# 7-Latching_IMD.net
KiCad netlist of a schematic drawn in Altium Designer
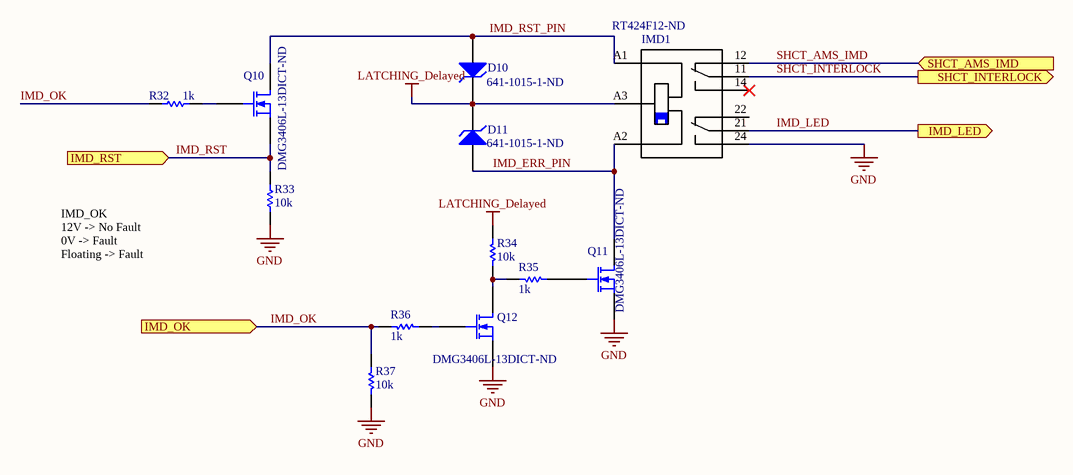
[diagram p0: 7-Latching IMD.SchDoc]

(export (version "E")
  (design (tool "Eeschema 10.0.6"))
  (components
    (comp (ref "D10")
      (value "D Zener")
      (footprint "DO214AC")
      (description "Zener Diode")
      (fields
        (field (name "SUPPLIER PART NUMBER 1") "641-1015-1-ND")
        (field (name "PUBLISHER") "Altium Limited")
      )
      (libsource (lib "Miscellaneous Devices") (part "D Zener"))
    )
    (comp (ref "D11")
      (value "D Zener")
      (footprint "DO214AC")
      (description "Zener Diode")
      (fields
        (field (name "SUPPLIER PART NUMBER 1") "641-1015-1-ND")
        (field (name "PUBLISHER") "Altium Limited")
      )
      (libsource (lib "Miscellaneous Devices") (part "D Zener"))
    )
    (comp (ref "IMD1")
      (value "5-1393243-4")
      (footprint "TE_5-1393243-4")
      (description "Electromechanical Relay 12VDC 240Ohm 15A DPDT __ 29mm 12.7mm 15.7mm__ THT Power Relay")
      (fields (field (name "MF") "TE Connectivity") (field (name "SUPPLIER PART NUMBER 1") "RT424F12-ND"))
      (libsource (lib "5-1393243-4") (part "5-1393243-4"))
    )
    (comp (ref "Q10")
      (value "~")
      (footprint "SOT-23_N")
      (description "N-Channel MOSFET")
      (fields
        (field (name "MANUFACTURER") "Infineon Technologies")
        (field (name "SUPPLIER PART NUMBER 1") "DMG3406L-13DICT-ND")
        (field (name "PUBLISHER") "Altium Limited")
      )
      (libsource (lib "Miscellaneous Devices") (part "MOSFET-N"))
    )
    (comp (ref "Q11")
      (value "~")
      (footprint "SOT-23_N")
      (description "N-Channel MOSFET")
      (fields
        (field (name "MANUFACTURER") "Infineon Technologies")
        (field (name "SUPPLIER PART NUMBER 1") "DMG3406L-13DICT-ND")
        (field (name "PUBLISHER") "Altium Limited")
      )
      (libsource (lib "Miscellaneous Devices") (part "MOSFET-N"))
    )
    (comp (ref "Q12")
      (value "~")
      (footprint "SOT-23_N")
      (description "N-Channel MOSFET")
      (fields
        (field (name "MANUFACTURER") "Infineon Technologies")
        (field (name "SUPPLIER PART NUMBER 1") "DMG3406L-13DICT-ND")
        (field (name "PUBLISHER") "Altium Limited")
      )
      (libsource (lib "Miscellaneous Devices") (part "MOSFET-N"))
    )
    (comp (ref "R32")
      (value "1k")
      (footprint "1608[0603]")
      (description "RES SMD 100 OHM 5% 1/4W 0603")
      (fields
        (field (name "MANUFACTURER") "Rohm Semiconductor")
        (field (name "MANUFACTURER PART NUMBER") "ESR03EZPJ101")
        (field (name "PUBLISHER") "Altium Limited")
      )
      (libsource (lib "Miscellaneous Devices") (part "Res1"))
    )
    (comp (ref "R33")
      (value "10k")
      (footprint "1608[0603]")
      (description "RES SMD 10K OHM 5% 1/4W 0603")
      (fields
        (field (name "MANUFACTURER") "Rohm Semiconductor")
        (field (name "MANUFACTURER PART NUMBER") "ESR03EZPJ103")
        (field (name "PUBLISHER") "Altium Limited")
      )
      (libsource (lib "Miscellaneous Devices") (part "Res1"))
    )
    (comp (ref "R34")
      (value "RHM1.0KDCT-ND")
      (footprint "1608[0603]")
      (description "RES SMD 1.0K OHM 5% 1/4W 0603")
      (fields
        (field (name "MANUFACTURER") "Rohm Semiconductor")
        (field (name "MANUFACTURER PART NUMBER") "ESR03EZPJ102")
        (field (name "RESISTANCE (OHMS)") "10k")
      )
      (libsource (lib "Miscellaneous Devices") (part "Res1"))
    )
    (comp (ref "R35")
      (value "1k")
      (footprint "1608[0603]")
      (description "RES SMD 100 OHM 5% 1/4W 0603")
      (fields
        (field (name "MANUFACTURER") "Rohm Semiconductor")
        (field (name "MANUFACTURER PART NUMBER") "ESR03EZPJ101")
        (field (name "PUBLISHER") "Altium Limited")
      )
      (libsource (lib "Miscellaneous Devices") (part "Res1"))
    )
    (comp (ref "R36")
      (value "1k")
      (footprint "1608[0603]")
      (description "RES SMD 100 OHM 5% 1/4W 0603")
      (fields
        (field (name "MANUFACTURER") "Rohm Semiconductor")
        (field (name "MANUFACTURER PART NUMBER") "ESR03EZPJ101")
        (field (name "PUBLISHER") "Altium Limited")
      )
      (libsource (lib "Miscellaneous Devices") (part "Res1"))
    )
    (comp (ref "R37")
      (value "10k")
      (footprint "1608[0603]")
      (description "RES SMD 2.2K OHM 5% 1/4W 0603")
      (fields
        (field (name "MANUFACTURER") "Rohm Semiconductor")
        (field (name "MANUFACTURER PART NUMBER") "ESR03EZPJ222")
        (field (name "PUBLISHER") "Altium Limited")
      )
      (libsource (lib "Miscellaneous Devices") (part "Res1"))
    )
  )
  (nets
    (net (code "1") (name "/IMD_ERR_PIN") (class "Default")
      (node (ref "D11") (pin "1") (pinfunction "A_1") (pintype "passive"))
      (node (ref "IMD1") (pin "A2") (pinfunction "A2_A2") (pintype "passive"))
      (node (ref "Q11") (pin "3") (pinfunction "D_3") (pintype "passive"))
    )
    (net (code "2") (name "/IMD_LED") (class "Default")
      (node (ref "IMD1") (pin "21") (pinfunction "21_21") (pintype "passive"))
    )
    (net (code "3") (name "/IMD_OK") (class "Default")
      (node (ref "R32") (pin "1") (pinfunction "1_1") (pintype "passive"))
      (node (ref "R36") (pin "2") (pinfunction "2_2") (pintype "passive"))
      (node (ref "R37") (pin "1") (pinfunction "1_1") (pintype "passive"))
    )
    (net (code "4") (name "/IMD_RST") (class "Default")
      (node (ref "Q10") (pin "2") (pinfunction "S_2") (pintype "passive"))
      (node (ref "R33") (pin "2") (pinfunction "2_2") (pintype "passive"))
    )
    (net (code "5") (name "/IMD_RST_PIN") (class "Default")
      (node (ref "D10") (pin "1") (pinfunction "A_1") (pintype "passive"))
      (node (ref "IMD1") (pin "A1") (pinfunction "A1_A1") (pintype "passive"))
      (node (ref "Q10") (pin "3") (pinfunction "D_3") (pintype "passive"))
    )
    (net (code "6") (name "/SHCT_AMS_IMD") (class "Default")
      (node (ref "IMD1") (pin "12") (pinfunction "12_12") (pintype "passive"))
    )
    (net (code "7") (name "/SHCT_INTERLOCK") (class "Default")
      (node (ref "IMD1") (pin "11") (pinfunction "11_11") (pintype "passive"))
    )
    (net (code "8") (name "GND") (class "Default")
      (node (ref "IMD1") (pin "24") (pinfunction "24_24") (pintype "passive"))
      (node (ref "Q11") (pin "2") (pinfunction "S_2") (pintype "passive"))
      (node (ref "Q12") (pin "2") (pinfunction "S_2") (pintype "passive"))
      (node (ref "R33") (pin "1") (pinfunction "1_1") (pintype "passive"))
      (node (ref "R37") (pin "2") (pinfunction "2_2") (pintype "passive"))
    )
    (net (code "9") (name "LATCHING_Delayed") (class "Default")
      (node (ref "D10") (pin "2") (pinfunction "K_2") (pintype "passive"))
      (node (ref "D11") (pin "2") (pinfunction "K_2") (pintype "passive"))
      (node (ref "IMD1") (pin "A3") (pinfunction "A3_A3") (pintype "passive"))
      (node (ref "R34") (pin "1") (pinfunction "1_1") (pintype "passive"))
    )
    (net (code "10") (name "Net-(Q10-G)") (class "Default")
      (node (ref "Q10") (pin "1") (pinfunction "G_1") (pintype "passive"))
      (node (ref "R32") (pin "2") (pinfunction "2_2") (pintype "passive"))
    )
    (net (code "11") (name "Net-(Q11-G)") (class "Default")
      (node (ref "Q11") (pin "1") (pinfunction "G_1") (pintype "passive"))
      (node (ref "R35") (pin "1") (pinfunction "1_1") (pintype "passive"))
    )
    (net (code "12") (name "Net-(Q12-D)") (class "Default")
      (node (ref "Q12") (pin "3") (pinfunction "D_3") (pintype "passive"))
      (node (ref "R34") (pin "2") (pinfunction "2_2") (pintype "passive"))
      (node (ref "R35") (pin "2") (pinfunction "2_2") (pintype "passive"))
    )
    (net (code "13") (name "Net-(Q12-G)") (class "Default")
      (node (ref "Q12") (pin "1") (pinfunction "G_1") (pintype "passive"))
      (node (ref "R36") (pin "1") (pinfunction "1_1") (pintype "passive"))
    )
    (net (code "14") (name "unconnected-(IMD1-Pad14)") (class "Default")
      (node (ref "IMD1") (pin "14") (pinfunction "14_14") (pintype "passive+no_connect"))
    )
    (net (code "15") (name "unconnected-(IMD1-Pad22)") (class "Default")
      (node (ref "IMD1") (pin "22") (pinfunction "22_22") (pintype "passive"))
    )
  )
)
